# LNA_BFU500.net
KiCad netlist of a schematic drawn in Altium Designer
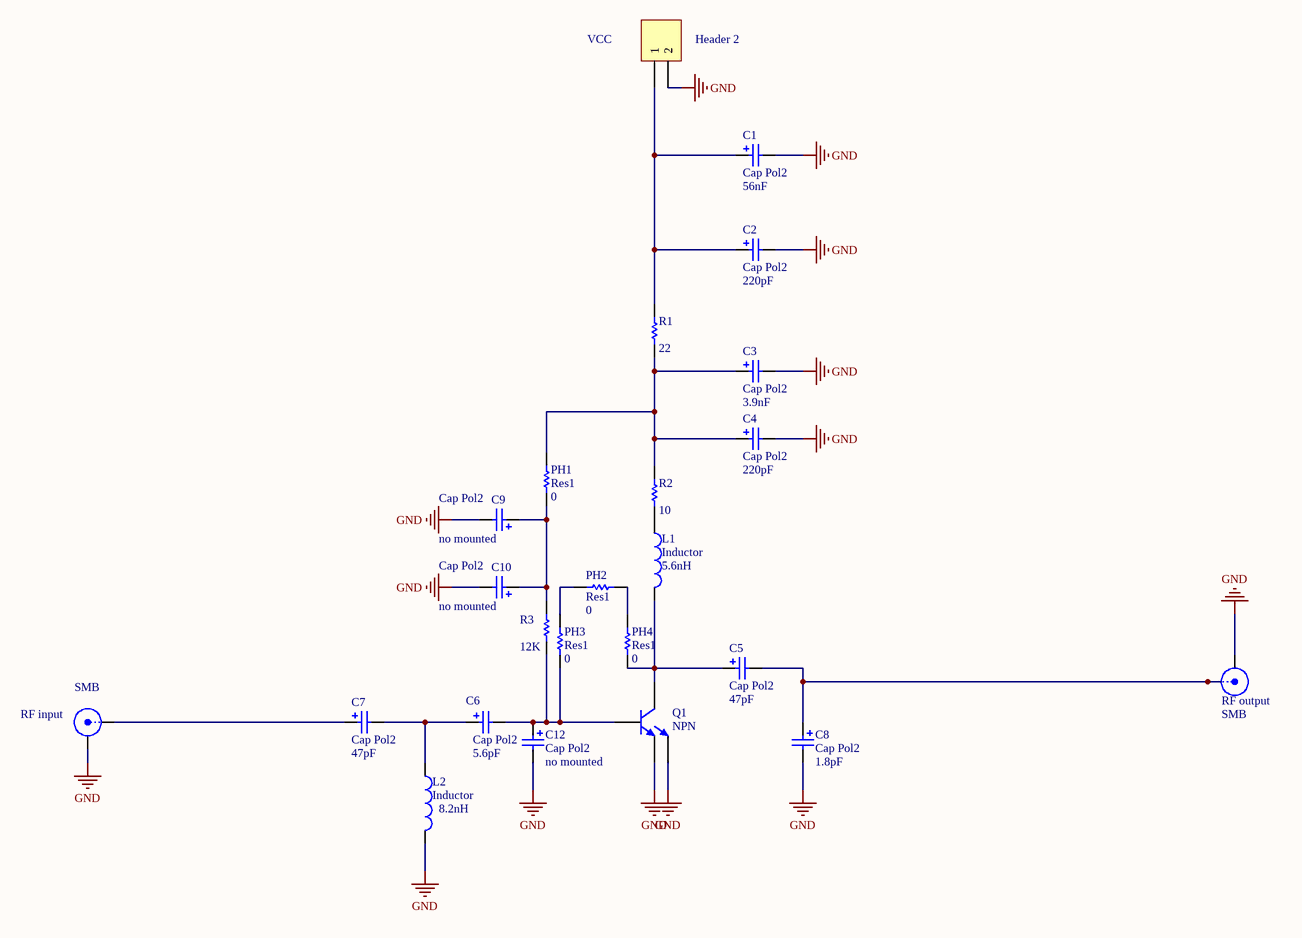
[diagram p0: LNA_BFU500.SchDoc]

(export (version "E")
  (design (tool "Eeschema 10.0.6"))
  (components
    (comp (ref "C1")
      (value "Cap Pol2")
      (footprint "6-0805_N")
      (description "Polarized Capacitor (Axial)")
      (fields (field (name "ALTIUM_VALUE") "56nF") (field (name "PUBLISHER") "Altium Limited"))
      (libsource (lib "PCB_Project") (part "Cap Pol2_1"))
    )
    (comp (ref "C2")
      (value "Cap Pol2")
      (footprint "6-0805_N")
      (description "Polarized Capacitor (Axial)")
      (fields (field (name "ALTIUM_VALUE") "220pF") (field (name "PUBLISHER") "Altium Limited"))
      (libsource (lib "PCB_Project") (part "Cap Pol2_1"))
    )
    (comp (ref "C3")
      (value "Cap Pol2")
      (footprint "6-0805_N")
      (description "Polarized Capacitor (Axial)")
      (fields (field (name "ALTIUM_VALUE") "3.9nF") (field (name "PUBLISHER") "Altium Limited"))
      (libsource (lib "PCB_Project") (part "Cap Pol2_1"))
    )
    (comp (ref "C4")
      (value "Cap Pol2")
      (footprint "6-0805_N")
      (description "Polarized Capacitor (Axial)")
      (fields (field (name "ALTIUM_VALUE") "220pF") (field (name "PUBLISHER") "Altium Limited"))
      (libsource (lib "PCB_Project") (part "Cap Pol2_1"))
    )
    (comp (ref "C5")
      (value "Cap Pol2")
      (footprint "6-0805_N")
      (description "Polarized Capacitor (Axial)")
      (fields (field (name "ALTIUM_VALUE") "47pF") (field (name "PUBLISHER") "Altium Limited"))
      (libsource (lib "PCB_Project") (part "Cap Pol2_1"))
    )
    (comp (ref "C6")
      (value "Cap Pol2")
      (footprint "6-0805_N")
      (description "Polarized Capacitor (Axial)")
      (fields (field (name "ALTIUM_VALUE") "5.6pF") (field (name "PUBLISHER") "Altium Limited"))
      (libsource (lib "PCB_Project") (part "Cap Pol2_1"))
    )
    (comp (ref "C7")
      (value "Cap Pol2")
      (footprint "6-0805_N")
      (description "Polarized Capacitor (Axial)")
      (fields (field (name "ALTIUM_VALUE") "47pF") (field (name "PUBLISHER") "Altium Limited"))
      (libsource (lib "PCB_Project") (part "Cap Pol2_1"))
    )
    (comp (ref "C8")
      (value "Cap Pol2")
      (footprint "6-0805_N")
      (description "Polarized Capacitor (Axial)")
      (fields (field (name "ALTIUM_VALUE") "1.8pF") (field (name "PUBLISHER") "Altium Limited"))
      (libsource (lib "PCB_Project") (part "Cap Pol2_1"))
    )
    (comp (ref "C9")
      (value "Cap Pol2")
      (footprint "6-0805_N")
      (description "Polarized Capacitor (Axial)")
      (fields (field (name "ALTIUM_VALUE") "no mounted") (field (name "PUBLISHER") "Altium Limited"))
      (libsource (lib "LNA_BFU550") (part "Cap Pol2_7"))
    )
    (comp (ref "C10")
      (value "Cap Pol2")
      (footprint "6-0805_N")
      (description "Polarized Capacitor (Axial)")
      (fields (field (name "ALTIUM_VALUE") "no mounted") (field (name "PUBLISHER") "Altium Limited"))
      (libsource (lib "LNA_BFU550") (part "Cap Pol2_7"))
    )
    (comp (ref "C12")
      (value "Cap Pol2")
      (footprint "6-0805_N")
      (description "Polarized Capacitor (Axial)")
      (fields (field (name "ALTIUM_VALUE") "no mounted") (field (name "PUBLISHER") "Altium Limited"))
      (libsource (lib "LNA_BFU550") (part "Cap Pol2_7"))
    )
    (comp (ref "L1")
      (value "Inductor")
      (footprint "6-0805_N")
      (fields (field (name "ALTIUM_VALUE") "5.6nH") (field (name "PUBLISHER") "Altium Limited"))
      (libsource (lib "PCB_Project") (part "Inductor"))
    )
    (comp (ref "L2")
      (value "Inductor")
      (footprint "6-0805_N")
      (fields (field (name "ALTIUM_VALUE") "8.2nH") (field (name "PUBLISHER") "Altium Limited"))
      (libsource (lib "PCB_Project") (part "Inductor"))
    )
    (comp (ref "PH1")
      (value "Res1")
      (footprint "6-0805_N")
      (description "Resistor")
      (fields (field (name "ALTIUM_VALUE") "0") (field (name "PUBLISHER") "Altium Limited"))
      (libsource (lib "LNA_BFU550") (part "Res1_1"))
    )
    (comp (ref "PH2")
      (value "Res1")
      (footprint "6-0805_N")
      (description "Resistor")
      (fields (field (name "ALTIUM_VALUE") "0") (field (name "PUBLISHER") "Altium Limited"))
      (libsource (lib "LNA_BFU550") (part "Res1_1"))
    )
    (comp (ref "PH3")
      (value "Res1")
      (footprint "6-0805_N")
      (description "Resistor")
      (fields (field (name "ALTIUM_VALUE") "0") (field (name "PUBLISHER") "Altium Limited"))
      (libsource (lib "LNA_BFU550") (part "Res1_1"))
    )
    (comp (ref "PH4")
      (value "Res1")
      (footprint "6-0805_N")
      (description "Resistor")
      (fields (field (name "ALTIUM_VALUE") "0") (field (name "PUBLISHER") "Altium Limited"))
      (libsource (lib "LNA_BFU550") (part "Res1_1"))
    )
    (comp (ref "Q1")
      (value "NPN")
      (footprint "SOT-143_N")
      (description "NPN Bipolar Transistor")
      (fields (field (name "PUBLISHER") "Altium Limited"))
      (libsource (lib "LNA_BFU550") (part "NPN"))
    )
    (comp (ref "R1")
      (value "22")
      (footprint "6-0805_N")
      (description "Resistor")
      (fields (field (name "PUBLISHER") "Altium Limited"))
      (libsource (lib "PCB_Project") (part "Res1"))
    )
    (comp (ref "R2")
      (value "10")
      (footprint "6-0805_N")
      (description "Resistor")
      (fields (field (name "Comment") "0") (field (name "PUBLISHER") "Altium Limited"))
      (libsource (lib "PCB_Project") (part "Res1"))
    )
    (comp (ref "R3")
      (value "12K")
      (footprint "6-0805_N")
      (description "Resistor")
      (fields (field (name "Comment") "0") (field (name "PUBLISHER") "Altium Limited"))
      (libsource (lib "PCB_Project") (part "Res1"))
    )
    (comp (ref "RF input")
      (value "SMB")
      (footprint "SMA-142-0701-851_V2")
      (description "SMB Straight Connector")
      (fields (field (name "PUBLISHER") "Altium Limited"))
      (libsource (lib "PCB_Project") (part "SMB"))
    )
    (comp (ref "RF output")
      (value "SMB")
      (footprint "SMA-142-0701-851_V2")
      (description "SMB Straight Connector")
      (fields (field (name "PUBLISHER") "Altium Limited"))
      (libsource (lib "PCB_Project") (part "SMB"))
    )
    (comp (ref "VCC")
      (value "Header 2")
      (footprint "HDR1X2")
      (description "Header, 2-Pin")
      (fields (field (name "PUBLISHER") "Altium Limited"))
      (libsource (lib "PCB_Project") (part "Header 2"))
    )
  )
  (nets
    (net (code "1") (name "GND") (class "Default")
      (node (ref "C1") (pin "2") (pinfunction "2_2") (pintype "passive"))
      (node (ref "C10") (pin "2") (pinfunction "2_2") (pintype "passive"))
      (node (ref "C12") (pin "2") (pinfunction "2_2") (pintype "passive"))
      (node (ref "C2") (pin "2") (pinfunction "2_2") (pintype "passive"))
      (node (ref "C3") (pin "2") (pinfunction "2_2") (pintype "passive"))
      (node (ref "C4") (pin "2") (pinfunction "2_2") (pintype "passive"))
      (node (ref "C8") (pin "2") (pinfunction "2_2") (pintype "passive"))
      (node (ref "C9") (pin "2") (pinfunction "2_2") (pintype "passive"))
      (node (ref "L2") (pin "2") (pinfunction "2_2") (pintype "passive"))
      (node (ref "Q1") (pin "3") (pinfunction "E_3") (pintype "passive"))
      (node (ref "Q1") (pin "4") (pinfunction "E_4") (pintype "passive"))
      (node (ref "RF input") (pin "2") (pinfunction "Y_2") (pintype "passive"))
      (node (ref "RF output") (pin "2") (pinfunction "Y_2") (pintype "passive"))
      (node (ref "VCC") (pin "2") (pinfunction "2_2") (pintype "passive"))
    )
    (net (code "2") (name "Net-(C1-Pad1)") (class "Default")
      (node (ref "C1") (pin "1") (pinfunction "1_1") (pintype "passive"))
      (node (ref "C2") (pin "1") (pinfunction "1_1") (pintype "passive"))
      (node (ref "R1") (pin "2") (pinfunction "2_2") (pintype "passive"))
      (node (ref "VCC") (pin "1") (pinfunction "1_1") (pintype "passive"))
    )
    (net (code "3") (name "Net-(C3-Pad1)") (class "Default")
      (node (ref "C3") (pin "1") (pinfunction "1_1") (pintype "passive"))
      (node (ref "C4") (pin "1") (pinfunction "1_1") (pintype "passive"))
      (node (ref "PH1") (pin "2") (pinfunction "2_2") (pintype "passive"))
      (node (ref "R1") (pin "1") (pinfunction "1_1") (pintype "passive"))
      (node (ref "R2") (pin "2") (pinfunction "2_2") (pintype "passive"))
    )
    (net (code "4") (name "Net-(C6-Pad1)") (class "Default")
      (node (ref "C6") (pin "1") (pinfunction "1_1") (pintype "passive"))
      (node (ref "C7") (pin "2") (pinfunction "2_2") (pintype "passive"))
      (node (ref "L2") (pin "1") (pinfunction "1_1") (pintype "passive"))
    )
    (net (code "5") (name "Net-(C10-Pad1)") (class "Default")
      (node (ref "C10") (pin "1") (pinfunction "1_1") (pintype "passive"))
      (node (ref "C9") (pin "1") (pinfunction "1_1") (pintype "passive"))
      (node (ref "PH1") (pin "1") (pinfunction "1_1") (pintype "passive"))
      (node (ref "R3") (pin "2") (pinfunction "2_2") (pintype "passive"))
    )
    (net (code "6") (name "Net-(L1-Pad1)") (class "Default")
      (node (ref "L1") (pin "1") (pinfunction "1_1") (pintype "passive"))
      (node (ref "R2") (pin "1") (pinfunction "1_1") (pintype "passive"))
    )
    (net (code "7") (name "Net-(PH2-Pad1)") (class "Default")
      (node (ref "PH2") (pin "1") (pinfunction "1_1") (pintype "passive"))
      (node (ref "PH3") (pin "2") (pinfunction "2_2") (pintype "passive"))
    )
    (net (code "8") (name "Net-(PH2-Pad2)") (class "Default")
      (node (ref "PH2") (pin "2") (pinfunction "2_2") (pintype "passive"))
      (node (ref "PH4") (pin "2") (pinfunction "2_2") (pintype "passive"))
    )
    (net (code "9") (name "Net-(Q1-B)") (class "Default")
      (node (ref "C12") (pin "1") (pinfunction "1_1") (pintype "passive"))
      (node (ref "C6") (pin "2") (pinfunction "2_2") (pintype "passive"))
      (node (ref "PH3") (pin "1") (pinfunction "1_1") (pintype "passive"))
      (node (ref "Q1") (pin "2") (pinfunction "B_2") (pintype "passive"))
      (node (ref "R3") (pin "1") (pinfunction "1_1") (pintype "passive"))
    )
    (net (code "10") (name "Net-(Q1-C)") (class "Default")
      (node (ref "C5") (pin "1") (pinfunction "1_1") (pintype "passive"))
      (node (ref "L1") (pin "2") (pinfunction "2_2") (pintype "passive"))
      (node (ref "PH4") (pin "1") (pinfunction "1_1") (pintype "passive"))
      (node (ref "Q1") (pin "1") (pinfunction "C_1") (pintype "passive"))
    )
    (net (code "11") (name "Net-(RF input-X)") (class "Default")
      (node (ref "C7") (pin "1") (pinfunction "1_1") (pintype "passive"))
      (node (ref "RF input") (pin "1") (pinfunction "X_1") (pintype "passive"))
    )
    (net (code "12") (name "Net-(RF output-X)") (class "Default")
      (node (ref "C5") (pin "2") (pinfunction "2_2") (pintype "passive"))
      (node (ref "C8") (pin "1") (pinfunction "1_1") (pintype "passive"))
      (node (ref "RF output") (pin "1") (pinfunction "X_1") (pintype "passive"))
    )
  )
)
